# POWER.net
KiCad netlist of a schematic drawn in Altium Designer
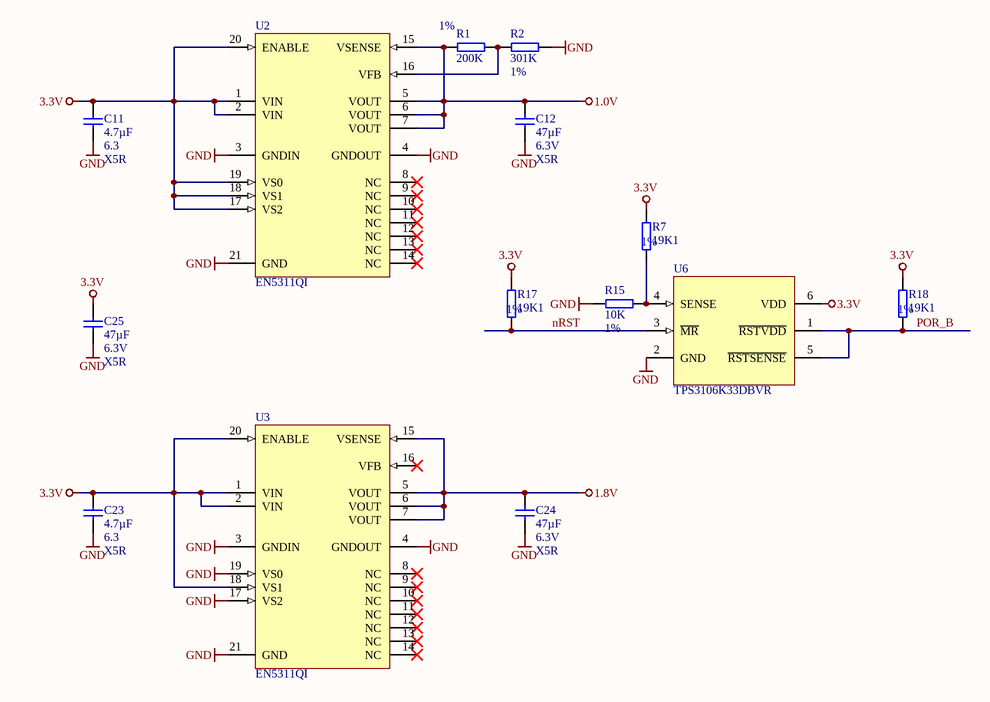
[diagram p0: POWER.SchDoc]

(export (version "E")
  (design (tool "Eeschema 10.0.6"))
  (components
    (comp (ref "C11")
      (value "4.7µF")
      (footprint "CAPC1005X60N")
      (description "KON 4.7µF 6.3V X5R SMD 20%")
      (fields
        (field (name "VOLTAGE") "6.3")
        (field (name "TECHNOLOGY") "X5R")
        (field (name "TOLERANCE") "20%")
      )
      (libsource (lib "TE") (part "CAP-NP"))
    )
    (comp (ref "C12")
      (value "47µF")
      (footprint "CAPC2012X135N")
      (description "KON 47µF 6,3V  X5R SMD 20%")
      (fields
        (field (name "VOLTAGE") "6.3V")
        (field (name "TECHNOLOGY") "X5R")
        (field (name "TOLERANCE") "20%")
      )
      (libsource (lib "TE") (part "CAP-NP"))
    )
    (comp (ref "C23")
      (value "4.7µF")
      (footprint "CAPC1005X60N")
      (description "KON 4.7µF 6.3V X5R SMD 20%")
      (fields
        (field (name "VOLTAGE") "6.3")
        (field (name "TECHNOLOGY") "X5R")
        (field (name "TOLERANCE") "20%")
      )
      (libsource (lib "TE") (part "CAP-NP"))
    )
    (comp (ref "C24")
      (value "47µF")
      (footprint "CAPC2012X135N")
      (description "KON 47µF 6,3V  X5R SMD 20%")
      (fields
        (field (name "VOLTAGE") "6.3V")
        (field (name "TECHNOLOGY") "X5R")
        (field (name "TOLERANCE") "20%")
      )
      (libsource (lib "TE") (part "CAP-NP"))
    )
    (comp (ref "C25")
      (value "47µF")
      (footprint "CAPC2012X135N")
      (description "KON 47µF 6,3V  X5R SMD 20%")
      (fields
        (field (name "VOLTAGE") "6.3V")
        (field (name "TECHNOLOGY") "X5R")
        (field (name "TOLERANCE") "20%")
      )
      (libsource (lib "TE") (part "CAP-NP"))
    )
    (comp (ref "R1")
      (value "200K")
      (footprint "RESC1005X40N")
      (description "WID SMD 200K 1% 0,063W")
      (fields (field (name "TOLERANCE") "1%"))
      (libsource (lib "TE") (part "RES"))
    )
    (comp (ref "R2")
      (value "301K")
      (footprint "RESC1005X40N")
      (description "WID SMD 301K 1% 0,063W")
      (fields (field (name "TOLERANCE") "1%"))
      (libsource (lib "TE") (part "RES"))
    )
    (comp (ref "R7")
      (value "19K1")
      (footprint "RESC0603X26N")
      (description "WID SMD 19K1 1% 0,05W")
      (fields (field (name "TOLERANCE") "1%"))
      (libsource (lib "TE") (part "RES"))
    )
    (comp (ref "R15")
      (value "10K")
      (footprint "RESC0603X26N")
      (description "WID SMD 10K 1% 0,05W")
      (fields (field (name "TOLERANCE") "1%"))
      (libsource (lib "TE") (part "RES"))
    )
    (comp (ref "R17")
      (value "19K1")
      (footprint "RESC0603X26N")
      (description "WID SMD 19K1 1% 0,05W")
      (fields (field (name "TOLERANCE") "1%"))
      (libsource (lib "TE") (part "RES"))
    )
    (comp (ref "R18")
      (value "19K1")
      (footprint "RESC0603X26N")
      (description "WID SMD 19K1 1% 0,05W")
      (fields (field (name "TOLERANCE") "1%"))
      (libsource (lib "TE") (part "RES"))
    )
    (comp (ref "U2") (value "EN5311QI") (footprint "EN5311QI") (libsource (lib "TE") (part "EN5311QI")))
    (comp (ref "U3") (value "EN5311QI") (footprint "EN5311QI") (libsource (lib "TE") (part "EN5311QI")))
    (comp (ref "U6")
      (value "TPS3106K33DBVR")
      (footprint "SOT95P280X145-6N")
      (libsource (lib "TE") (part "TPS3106"))
    )
  )
  (nets
    (net (code "1") (name "/POR_B") (class "Default")
      (node (ref "R18") (pin "1") (pinfunction "1_1") (pintype "passive"))
      (node (ref "U6") (pin "1") (pinfunction "~{RSTVDD}_1") (pintype "open_collector"))
      (node (ref "U6") (pin "5") (pinfunction "~{RSTSENSE}_5") (pintype "open_collector"))
    )
    (net (code "2") (name "/nRST") (class "Default")
      (node (ref "R17") (pin "1") (pinfunction "1_1") (pintype "passive"))
      (node (ref "U6") (pin "3") (pinfunction "~{MR}_3") (pintype "input"))
    )
    (net (code "3") (name "1.0V") (class "Default")
      (node (ref "C12") (pin "1") (pinfunction "1_1") (pintype "passive"))
      (node (ref "R1") (pin "1") (pinfunction "1_1") (pintype "passive"))
      (node (ref "U2") (pin "15") (pinfunction "VSENSE_15") (pintype "input"))
      (node (ref "U2") (pin "5") (pinfunction "VOUT_5") (pintype "power_in"))
      (node (ref "U2") (pin "6") (pinfunction "VOUT_6") (pintype "power_in"))
      (node (ref "U2") (pin "7") (pinfunction "VOUT_7") (pintype "power_in"))
    )
    (net (code "4") (name "1.8V") (class "Default")
      (node (ref "C24") (pin "1") (pinfunction "1_1") (pintype "passive"))
      (node (ref "U3") (pin "15") (pinfunction "VSENSE_15") (pintype "input"))
      (node (ref "U3") (pin "5") (pinfunction "VOUT_5") (pintype "power_in"))
      (node (ref "U3") (pin "6") (pinfunction "VOUT_6") (pintype "power_in"))
      (node (ref "U3") (pin "7") (pinfunction "VOUT_7") (pintype "power_in"))
    )
    (net (code "5") (name "3.3V") (class "Default")
      (node (ref "C11") (pin "1") (pinfunction "1_1") (pintype "passive"))
      (node (ref "C23") (pin "1") (pinfunction "1_1") (pintype "passive"))
      (node (ref "C25") (pin "1") (pinfunction "1_1") (pintype "passive"))
      (node (ref "R17") (pin "2") (pinfunction "2_2") (pintype "passive"))
      (node (ref "R18") (pin "2") (pinfunction "2_2") (pintype "passive"))
      (node (ref "R7") (pin "2") (pinfunction "2_2") (pintype "passive"))
      (node (ref "U2") (pin "1") (pinfunction "VIN_1") (pintype "power_in"))
      (node (ref "U2") (pin "17") (pinfunction "VS2_17") (pintype "input"))
      (node (ref "U2") (pin "18") (pinfunction "VS1_18") (pintype "input"))
      (node (ref "U2") (pin "19") (pinfunction "VS0_19") (pintype "input"))
      (node (ref "U2") (pin "2") (pinfunction "VIN_2") (pintype "power_in"))
      (node (ref "U2") (pin "20") (pinfunction "ENABLE_20") (pintype "input"))
      (node (ref "U3") (pin "1") (pinfunction "VIN_1") (pintype "power_in"))
      (node (ref "U3") (pin "18") (pinfunction "VS1_18") (pintype "input"))
      (node (ref "U3") (pin "2") (pinfunction "VIN_2") (pintype "power_in"))
      (node (ref "U3") (pin "20") (pinfunction "ENABLE_20") (pintype "input"))
      (node (ref "U6") (pin "6") (pinfunction "VDD_6") (pintype "power_in"))
    )
    (net (code "6") (name "GND") (class "Default")
      (node (ref "C11") (pin "2") (pinfunction "2_2") (pintype "passive"))
      (node (ref "C12") (pin "2") (pinfunction "2_2") (pintype "passive"))
      (node (ref "C23") (pin "2") (pinfunction "2_2") (pintype "passive"))
      (node (ref "C24") (pin "2") (pinfunction "2_2") (pintype "passive"))
      (node (ref "C25") (pin "2") (pinfunction "2_2") (pintype "passive"))
      (node (ref "R15") (pin "1") (pinfunction "1_1") (pintype "passive"))
      (node (ref "R2") (pin "2") (pinfunction "2_2") (pintype "passive"))
      (node (ref "U2") (pin "21") (pinfunction "GND_21") (pintype "power_in"))
      (node (ref "U2") (pin "3") (pinfunction "GNDIN_3") (pintype "power_in"))
      (node (ref "U2") (pin "4") (pinfunction "GNDOUT_4") (pintype "power_in"))
      (node (ref "U3") (pin "17") (pinfunction "VS2_17") (pintype "input"))
      (node (ref "U3") (pin "19") (pinfunction "VS0_19") (pintype "input"))
      (node (ref "U3") (pin "21") (pinfunction "GND_21") (pintype "power_in"))
      (node (ref "U3") (pin "3") (pinfunction "GNDIN_3") (pintype "power_in"))
      (node (ref "U3") (pin "4") (pinfunction "GNDOUT_4") (pintype "power_in"))
      (node (ref "U6") (pin "2") (pinfunction "GND_2") (pintype "power_in"))
    )
    (net (code "7") (name "Net-(U2-VFB)") (class "Default")
      (node (ref "R1") (pin "2") (pinfunction "2_2") (pintype "passive"))
      (node (ref "R2") (pin "1") (pinfunction "1_1") (pintype "passive"))
      (node (ref "U2") (pin "16") (pinfunction "VFB_16") (pintype "input"))
    )
    (net (code "8") (name "Net-(U6-SENSE)") (class "Default")
      (node (ref "R15") (pin "2") (pinfunction "2_2") (pintype "passive"))
      (node (ref "R7") (pin "1") (pinfunction "1_1") (pintype "passive"))
      (node (ref "U6") (pin "4") (pinfunction "SENSE_4") (pintype "input"))
    )
    (net (code "9") (name "unconnected-(U2-NC-Pad8)") (class "Default")
      (node (ref "U2") (pin "8") (pinfunction "NC_8") (pintype "passive+no_connect"))
    )
    (net (code "10") (name "unconnected-(U2-NC-Pad9)") (class "Default")
      (node (ref "U2") (pin "9") (pinfunction "NC_9") (pintype "passive+no_connect"))
    )
    (net (code "11") (name "unconnected-(U2-NC-Pad10)") (class "Default")
      (node (ref "U2") (pin "10") (pinfunction "NC_10") (pintype "passive+no_connect"))
    )
    (net (code "12") (name "unconnected-(U2-NC-Pad11)") (class "Default")
      (node (ref "U2") (pin "11") (pinfunction "NC_11") (pintype "passive+no_connect"))
    )
    (net (code "13") (name "unconnected-(U2-NC-Pad12)") (class "Default")
      (node (ref "U2") (pin "12") (pinfunction "NC_12") (pintype "passive+no_connect"))
    )
    (net (code "14") (name "unconnected-(U2-NC-Pad13)") (class "Default")
      (node (ref "U2") (pin "13") (pinfunction "NC_13") (pintype "passive+no_connect"))
    )
    (net (code "15") (name "unconnected-(U2-NC-Pad14)") (class "Default")
      (node (ref "U2") (pin "14") (pinfunction "NC_14") (pintype "passive+no_connect"))
    )
    (net (code "16") (name "unconnected-(U3-NC-Pad8)") (class "Default")
      (node (ref "U3") (pin "8") (pinfunction "NC_8") (pintype "passive+no_connect"))
    )
    (net (code "17") (name "unconnected-(U3-NC-Pad9)") (class "Default")
      (node (ref "U3") (pin "9") (pinfunction "NC_9") (pintype "passive+no_connect"))
    )
    (net (code "18") (name "unconnected-(U3-NC-Pad10)") (class "Default")
      (node (ref "U3") (pin "10") (pinfunction "NC_10") (pintype "passive+no_connect"))
    )
    (net (code "19") (name "unconnected-(U3-NC-Pad11)") (class "Default")
      (node (ref "U3") (pin "11") (pinfunction "NC_11") (pintype "passive+no_connect"))
    )
    (net (code "20") (name "unconnected-(U3-NC-Pad12)") (class "Default")
      (node (ref "U3") (pin "12") (pinfunction "NC_12") (pintype "passive+no_connect"))
    )
    (net (code "21") (name "unconnected-(U3-NC-Pad13)") (class "Default")
      (node (ref "U3") (pin "13") (pinfunction "NC_13") (pintype "passive+no_connect"))
    )
    (net (code "22") (name "unconnected-(U3-NC-Pad14)") (class "Default")
      (node (ref "U3") (pin "14") (pinfunction "NC_14") (pintype "passive+no_connect"))
    )
    (net (code "23") (name "unconnected-(U3-VFB-Pad16)") (class "Default")
      (node (ref "U3") (pin "16") (pinfunction "VFB_16") (pintype "input+no_connect"))
    )
  )
)
